# bms_master.net
KiCad netlist of a schematic drawn in EAGLE
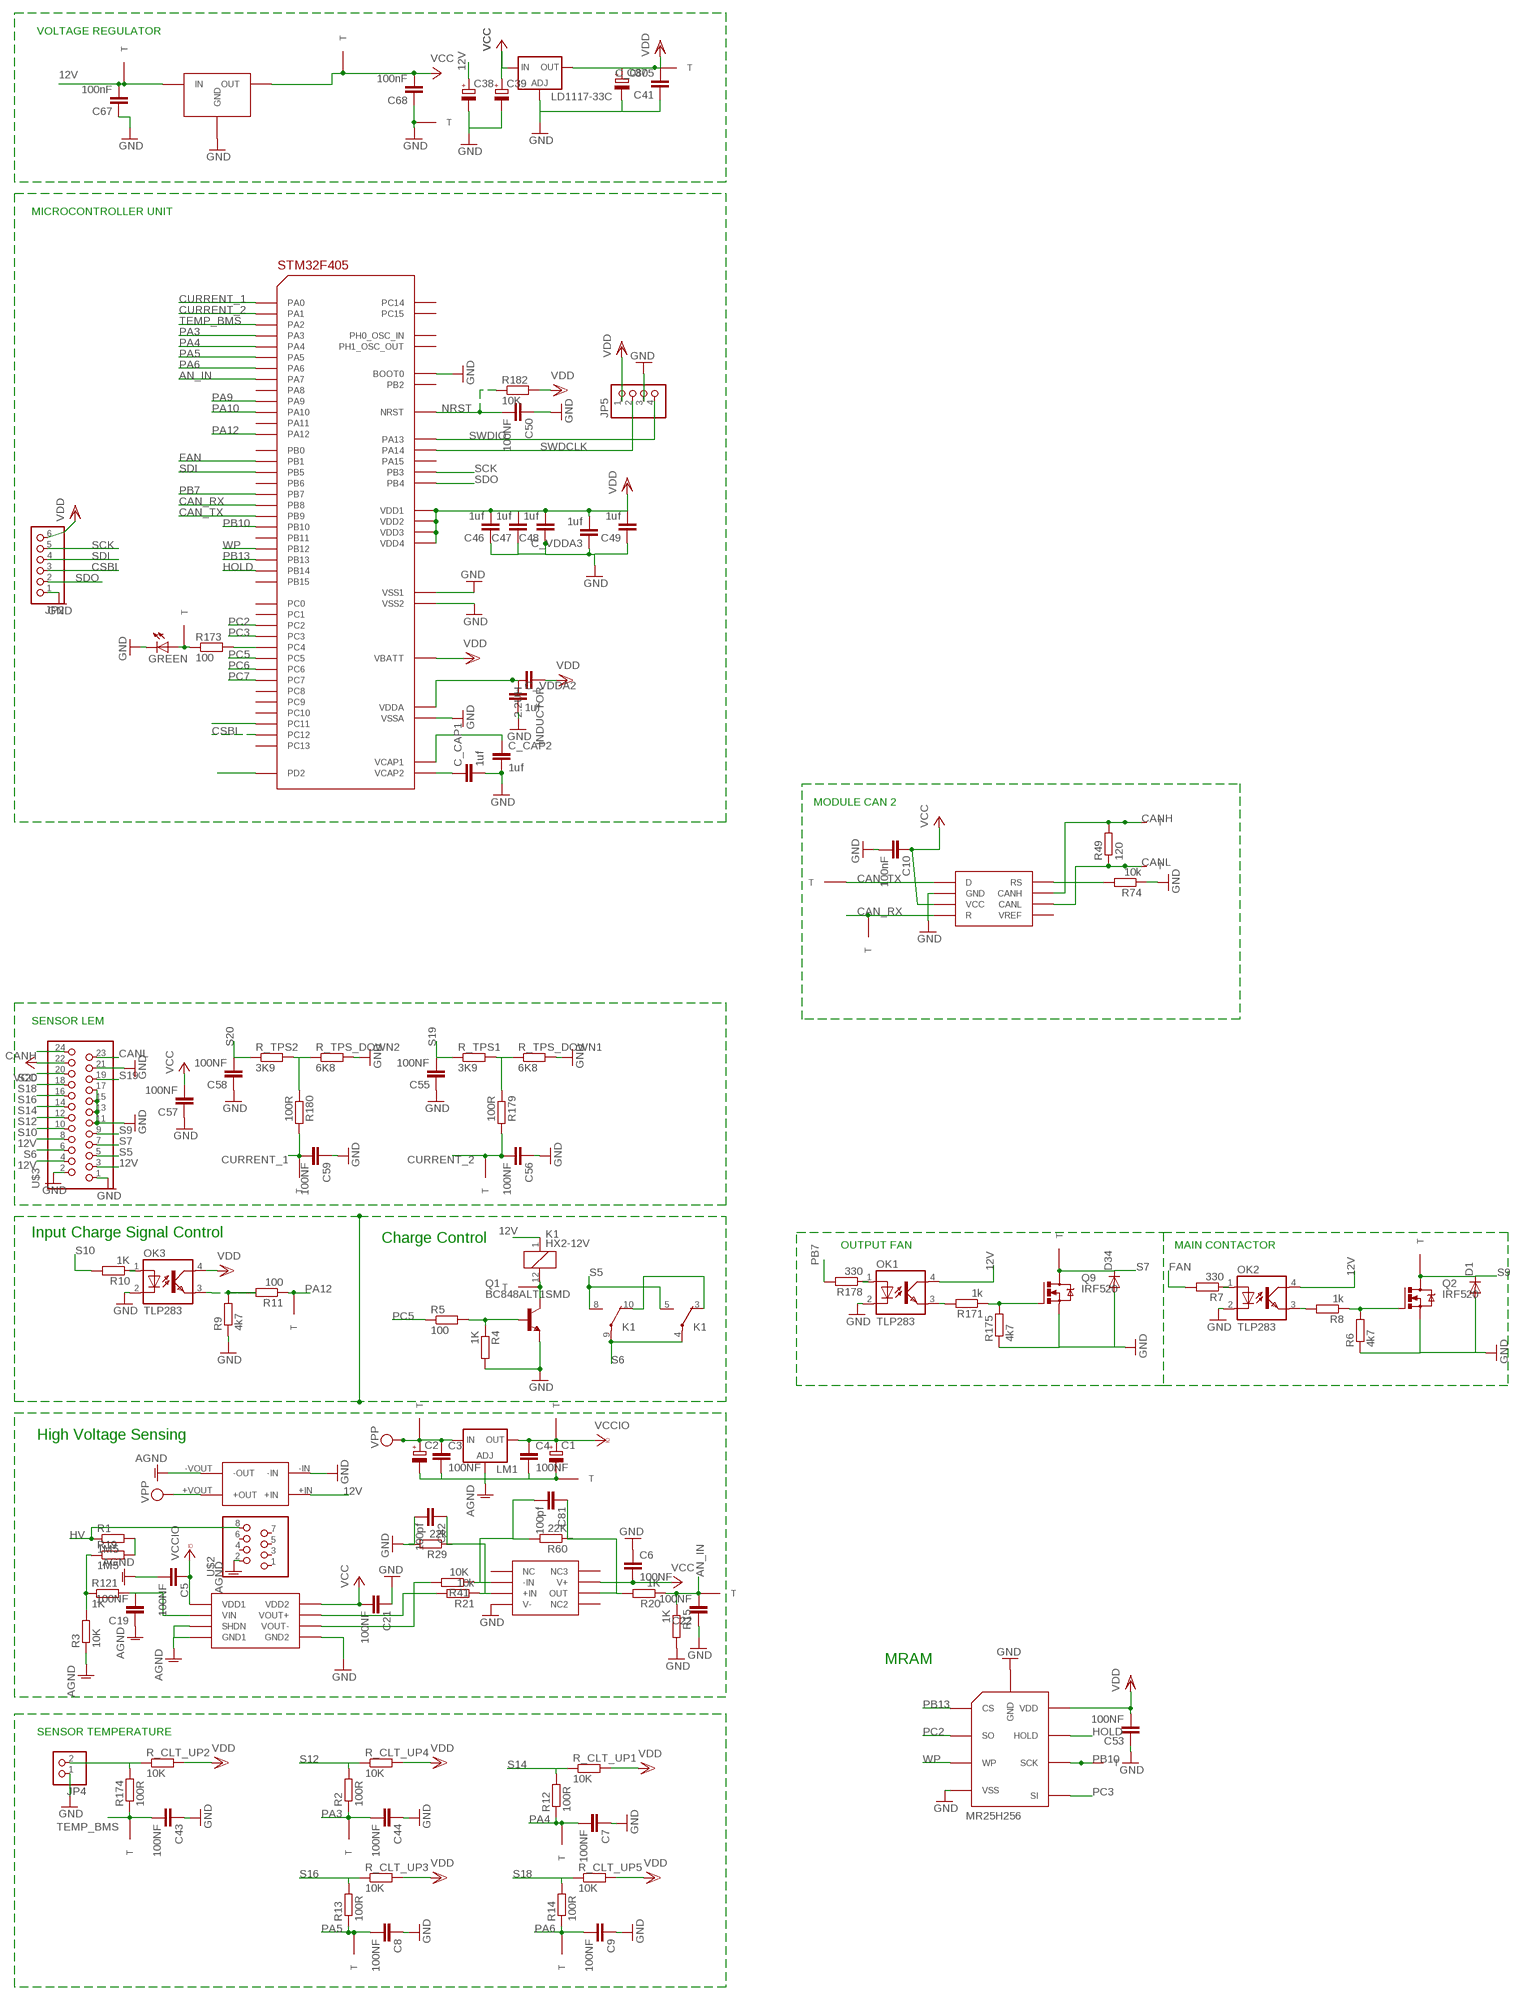
[diagram p0: schematic, sheet 1]

(export (version "E")
  (design (tool "Eeschema 10.0.6"))
  (components
    (comp (ref "C1")
      (value "CPOL-EU153CLV-0605")
      (footprint "eagle-import:153CLV-0605")
      (libsource (lib "eagle-import") (part "CPOL-EU153CLV-0605"))
    )
    (comp (ref "C2")
      (value "CPOL-EU153CLV-0810")
      (footprint "eagle-import:153CLV-0810")
      (libsource (lib "eagle-import") (part "CPOL-EU153CLV-0810"))
    )
    (comp (ref "C3")
      (value "100NF")
      (footprint "eagle-import:C_0805")
      (libsource (lib "eagle-import") (part "C_0805"))
    )
    (comp (ref "C4")
      (value "100NF")
      (footprint "eagle-import:C_0805")
      (libsource (lib "eagle-import") (part "C_0805"))
    )
    (comp (ref "C5")
      (value "100NF")
      (footprint "eagle-import:C_0805")
      (libsource (lib "eagle-import") (part "C_0805"))
    )
    (comp (ref "C6")
      (value "100NF")
      (footprint "eagle-import:C_0805")
      (libsource (lib "eagle-import") (part "C_0805"))
    )
    (comp (ref "C7")
      (value "100NF")
      (footprint "eagle-import:C_0805")
      (libsource (lib "eagle-import") (part "C_0805"))
    )
    (comp (ref "C8")
      (value "100NF")
      (footprint "eagle-import:C_0805")
      (libsource (lib "eagle-import") (part "C_0805"))
    )
    (comp (ref "C9")
      (value "100NF")
      (footprint "eagle-import:C_0805")
      (libsource (lib "eagle-import") (part "C_0805"))
    )
    (comp (ref "C10")
      (value "100nF")
      (footprint "eagle-import:C_0805")
      (libsource (lib "eagle-import") (part "C_0805"))
    )
    (comp (ref "C19")
      (value "100NF")
      (footprint "eagle-import:C_0805")
      (libsource (lib "eagle-import") (part "C_0805"))
    )
    (comp (ref "C21")
      (value "100NF")
      (footprint "eagle-import:C_0805")
      (libsource (lib "eagle-import") (part "C_0805"))
    )
    (comp (ref "C22")
      (value "100NF")
      (footprint "eagle-import:C_0805")
      (libsource (lib "eagle-import") (part "C_0805"))
    )
    (comp (ref "C37")
      (value "CPOL-EU153CLV-0605")
      (footprint "eagle-import:153CLV-0605")
      (libsource (lib "eagle-import") (part "CPOL-EU153CLV-0605"))
    )
    (comp (ref "C38")
      (value "CPOL-EU153CLV-0810")
      (footprint "eagle-import:153CLV-0810")
      (libsource (lib "eagle-import") (part "CPOL-EU153CLV-0810"))
    )
    (comp (ref "C39")
      (value "CPOL-EU153CLV-0605")
      (footprint "eagle-import:153CLV-0605")
      (libsource (lib "eagle-import") (part "CPOL-EU153CLV-0605"))
    )
    (comp (ref "C41")
      (value "C_0805")
      (footprint "eagle-import:C_0805")
      (libsource (lib "eagle-import") (part "C_0805"))
    )
    (comp (ref "C43")
      (value "100NF")
      (footprint "eagle-import:C_0805")
      (libsource (lib "eagle-import") (part "C_0805"))
    )
    (comp (ref "C44")
      (value "100NF")
      (footprint "eagle-import:C_0805")
      (libsource (lib "eagle-import") (part "C_0805"))
    )
    (comp (ref "C46")
      (value "1uf")
      (footprint "eagle-import:C_0805")
      (libsource (lib "eagle-import") (part "C_0805"))
    )
    (comp (ref "C47")
      (value "1uf")
      (footprint "eagle-import:C_0805")
      (libsource (lib "eagle-import") (part "C_0805"))
    )
    (comp (ref "C48")
      (value "1uf")
      (footprint "eagle-import:C_0805")
      (libsource (lib "eagle-import") (part "C_0805"))
    )
    (comp (ref "C49")
      (value "1uf")
      (footprint "eagle-import:C_0805")
      (libsource (lib "eagle-import") (part "C_0805"))
    )
    (comp (ref "C50")
      (value "100NF")
      (footprint "eagle-import:C_0805")
      (libsource (lib "eagle-import") (part "C_0805"))
    )
    (comp (ref "C53")
      (value "100NF")
      (footprint "eagle-import:C_0805")
      (libsource (lib "eagle-import") (part "C_0805"))
    )
    (comp (ref "C55")
      (value "100NF")
      (footprint "eagle-import:C_0805")
      (libsource (lib "eagle-import") (part "C_0805"))
    )
    (comp (ref "C56")
      (value "100NF")
      (footprint "eagle-import:C_0805")
      (libsource (lib "eagle-import") (part "C_0805"))
    )
    (comp (ref "C57")
      (value "100NF")
      (footprint "eagle-import:C_0805")
      (libsource (lib "eagle-import") (part "C_0805"))
    )
    (comp (ref "C58")
      (value "100NF")
      (footprint "eagle-import:C_0805")
      (libsource (lib "eagle-import") (part "C_0805"))
    )
    (comp (ref "C59")
      (value "100NF")
      (footprint "eagle-import:C_0805")
      (libsource (lib "eagle-import") (part "C_0805"))
    )
    (comp (ref "C67")
      (value "100nF")
      (footprint "eagle-import:C_0805")
      (libsource (lib "eagle-import") (part "C_0805"))
    )
    (comp (ref "C68")
      (value "100nF")
      (footprint "eagle-import:C_0805")
      (libsource (lib "eagle-import") (part "C_0805"))
    )
    (comp (ref "C81")
      (value "100pf")
      (footprint "eagle-import:C_0805")
      (libsource (lib "eagle-import") (part "C_0805"))
    )
    (comp (ref "C82")
      (value "100pf")
      (footprint "eagle-import:C_0805")
      (libsource (lib "eagle-import") (part "C_0805"))
    )
    (comp (ref "C_CAP1")
      (value "1uf")
      (footprint "eagle-import:C_0805")
      (libsource (lib "eagle-import") (part "C_0805"))
    )
    (comp (ref "C_CAP2")
      (value "1uf")
      (footprint "eagle-import:C_0805")
      (libsource (lib "eagle-import") (part "C_0805"))
    )
    (comp (ref "C_VDDA2")
      (value "1uf")
      (footprint "eagle-import:C_0805")
      (libsource (lib "eagle-import") (part "C_0805"))
    )
    (comp (ref "C_VDDA3")
      (value "1uf")
      (footprint "eagle-import:C_0805")
      (libsource (lib "eagle-import") (part "C_0805"))
    )
    (comp (ref "D1")
      (value "DIODE-SOD80C")
      (footprint "eagle-import:SOD80C")
      (libsource (lib "eagle-import") (part "DIODE-SOD80C"))
    )
    (comp (ref "D34")
      (value "DIODE-SOD80C")
      (footprint "eagle-import:SOD80C")
      (libsource (lib "eagle-import") (part "DIODE-SOD80C"))
    )
    (comp (ref "GREEN")
      (value "LED3MM")
      (footprint "eagle-import:LED3MM")
      (libsource (lib "eagle-import") (part "LED3MM"))
    )
    (comp (ref "INDUCTOR")
      (value "2.2UH")
      (footprint "eagle-import:C0805K")
      (libsource (lib "eagle-import") (part "C-EUC0805K"))
    )
    (comp (ref "JP2")
      (value "PINHD-1X6")
      (footprint "eagle-import:1X06")
      (libsource (lib "eagle-import") (part "PINHD-1X6"))
    )
    (comp (ref "JP4")
      (value "PINHD-1X2/90")
      (footprint "eagle-import:1X02_90")
      (libsource (lib "eagle-import") (part "PINHD-1X2/90"))
    )
    (comp (ref "JP5")
      (value "PINHD-1X4")
      (footprint "eagle-import:1X04")
      (libsource (lib "eagle-import") (part "PINHD-1X4"))
    )
    (comp (ref "K1")
      (value "HX2-12V")
      (footprint "eagle-import:HX")
      (libsource (lib "eagle-import") (part "HX2-12V"))
    )
    (comp (ref "LD1117-33C")
      (value "LM317MABDT")
      (footprint "eagle-import:DPACK@1")
      (libsource (lib "eagle-import") (part "v-reg_LM317?MABDT"))
    )
    (comp (ref "LM1")
      (value "LM317MABDT")
      (footprint "eagle-import:DPACK@1")
      (libsource (lib "eagle-import") (part "v-reg_LM317?MABDT"))
    )
    (comp (ref "OK1")
      (value "TLP283")
      (footprint "eagle-import:MINI-FLAT-4")
      (libsource (lib "eagle-import") (part "TLP283"))
    )
    (comp (ref "OK2")
      (value "TLP283")
      (footprint "eagle-import:MINI-FLAT-4")
      (libsource (lib "eagle-import") (part "TLP283"))
    )
    (comp (ref "OK3")
      (value "TLP283")
      (footprint "eagle-import:MINI-FLAT-4")
      (libsource (lib "eagle-import") (part "TLP283"))
    )
    (comp (ref "Q1")
      (value "BC848ALT1SMD")
      (footprint "eagle-import:SOT23")
      (libsource (lib "eagle-import") (part "BC848SMDALT1"))
    )
    (comp (ref "Q2")
      (value "IRF520")
      (footprint "eagle-import:D-PAK_TO252AA")
      (libsource (lib "eagle-import") (part "IRF520"))
    )
    (comp (ref "Q9")
      (value "IRF520")
      (footprint "eagle-import:D-PAK_TO252AA")
      (libsource (lib "eagle-import") (part "IRF520"))
    )
    (comp (ref "R1")
      (value "1M5")
      (footprint "eagle-import:R1210")
      (libsource (lib "eagle-import") (part "R_1210"))
    )
    (comp (ref "R2")
      (value "100R")
      (footprint "eagle-import:R_0805")
      (libsource (lib "eagle-import") (part "R_EU"))
    )
    (comp (ref "R3")
      (value "10K")
      (footprint "eagle-import:R1210")
      (libsource (lib "eagle-import") (part "R_1210"))
    )
    (comp (ref "R4")
      (value "1K")
      (footprint "eagle-import:R_0805")
      (libsource (lib "eagle-import") (part "R_EU"))
    )
    (comp (ref "R5")
      (value "100")
      (footprint "eagle-import:R_0805")
      (libsource (lib "eagle-import") (part "R_EU"))
    )
    (comp (ref "R6")
      (value "4k7")
      (footprint "eagle-import:R_0805")
      (libsource (lib "eagle-import") (part "R_EU"))
    )
    (comp (ref "R7")
      (value "330")
      (footprint "eagle-import:R_0805")
      (libsource (lib "eagle-import") (part "R_EU"))
    )
    (comp (ref "R8")
      (value "1k")
      (footprint "eagle-import:R_0805")
      (libsource (lib "eagle-import") (part "R_EU"))
    )
    (comp (ref "R9")
      (value "4k7")
      (footprint "eagle-import:R_0805")
      (libsource (lib "eagle-import") (part "R_EU"))
    )
    (comp (ref "R10")
      (value "1K")
      (footprint "eagle-import:R_0805")
      (libsource (lib "eagle-import") (part "R_EU"))
    )
    (comp (ref "R11")
      (value "100")
      (footprint "eagle-import:R_0805")
      (libsource (lib "eagle-import") (part "R_EU"))
    )
    (comp (ref "R12")
      (value "100R")
      (footprint "eagle-import:R_0805")
      (libsource (lib "eagle-import") (part "R_EU"))
    )
    (comp (ref "R13")
      (value "100R")
      (footprint "eagle-import:R_0805")
      (libsource (lib "eagle-import") (part "R_EU"))
    )
    (comp (ref "R14")
      (value "100R")
      (footprint "eagle-import:R_0805")
      (libsource (lib "eagle-import") (part "R_EU"))
    )
    (comp (ref "R15")
      (value "1K")
      (footprint "eagle-import:R_0805")
      (libsource (lib "eagle-import") (part "R_EU"))
    )
    (comp (ref "R19")
      (value "1M5")
      (footprint "eagle-import:R1210")
      (libsource (lib "eagle-import") (part "R_1210"))
    )
    (comp (ref "R20")
      (value "1K")
      (footprint "eagle-import:R_0805")
      (libsource (lib "eagle-import") (part "R_EU"))
    )
    (comp (ref "R21")
      (value "10k")
      (footprint "eagle-import:R_0805")
      (libsource (lib "eagle-import") (part "R_EU"))
    )
    (comp (ref "R29")
      (value "22k")
      (footprint "eagle-import:R_0805")
      (libsource (lib "eagle-import") (part "R_EU"))
    )
    (comp (ref "R41")
      (value "10K")
      (footprint "eagle-import:R_0805")
      (libsource (lib "eagle-import") (part "R_EU"))
    )
    (comp (ref "R49")
      (value "120")
      (footprint "eagle-import:0207_7")
      (libsource (lib "eagle-import") (part "R-EU_0207/7"))
    )
    (comp (ref "R60")
      (value "22K")
      (footprint "eagle-import:R_0805")
      (libsource (lib "eagle-import") (part "R_EU"))
    )
    (comp (ref "R74")
      (value "10k")
      (footprint "eagle-import:R_0805")
      (libsource (lib "eagle-import") (part "R_EU"))
    )
    (comp (ref "R121")
      (value "1K")
      (footprint "eagle-import:R_1210")
      (libsource (lib "eagle-import") (part "IVC_R_1210"))
    )
    (comp (ref "R171")
      (value "1k")
      (footprint "eagle-import:R_0805")
      (libsource (lib "eagle-import") (part "R_EU"))
    )
    (comp (ref "R173")
      (value "100")
      (footprint "eagle-import:R_0805")
      (libsource (lib "eagle-import") (part "R_EU"))
    )
    (comp (ref "R174")
      (value "100R")
      (footprint "eagle-import:R_0805")
      (libsource (lib "eagle-import") (part "R_EU"))
    )
    (comp (ref "R175")
      (value "4k7")
      (footprint "eagle-import:R_0805")
      (libsource (lib "eagle-import") (part "R_EU"))
    )
    (comp (ref "R178")
      (value "330")
      (footprint "eagle-import:R_0805")
      (libsource (lib "eagle-import") (part "R_EU"))
    )
    (comp (ref "R179")
      (value "100R")
      (footprint "eagle-import:R_0805")
      (libsource (lib "eagle-import") (part "R_EU"))
    )
    (comp (ref "R180")
      (value "100R")
      (footprint "eagle-import:R_0805")
      (libsource (lib "eagle-import") (part "R_EU"))
    )
    (comp (ref "R182")
      (value "10K")
      (footprint "eagle-import:R_0805")
      (libsource (lib "eagle-import") (part "R_EU"))
    )
    (comp (ref "R_CLT_UP1")
      (value "10K")
      (footprint "eagle-import:R_0805")
      (libsource (lib "eagle-import") (part "R_EU"))
    )
    (comp (ref "R_CLT_UP2")
      (value "10K")
      (footprint "eagle-import:R_0805")
      (libsource (lib "eagle-import") (part "R_EU"))
    )
    (comp (ref "R_CLT_UP3")
      (value "10K")
      (footprint "eagle-import:R_0805")
      (libsource (lib "eagle-import") (part "R_EU"))
    )
    (comp (ref "R_CLT_UP4")
      (value "10K")
      (footprint "eagle-import:R_0805")
      (libsource (lib "eagle-import") (part "R_EU"))
    )
    (comp (ref "R_CLT_UP5")
      (value "10K")
      (footprint "eagle-import:R_0805")
      (libsource (lib "eagle-import") (part "R_EU"))
    )
    (comp (ref "R_TPS1")
      (value "3K9")
      (footprint "eagle-import:R_0805")
      (libsource (lib "eagle-import") (part "R_EU"))
    )
    (comp (ref "R_TPS2")
      (value "3K9")
      (footprint "eagle-import:R_0805")
      (libsource (lib "eagle-import") (part "R_EU"))
    )
    (comp (ref "R_TPS_DOWN1")
      (value "6K8")
      (footprint "eagle-import:R_0805")
      (libsource (lib "eagle-import") (part "R_EU"))
    )
    (comp (ref "R_TPS_DOWN2")
      (value "6K8")
      (footprint "eagle-import:R_0805")
      (libsource (lib "eagle-import") (part "R_EU"))
    )
    (comp (ref "U$1")
      (value "NWD5-12")
      (footprint "eagle-import:NWD5")
      (libsource (lib "eagle-import") (part "NWD5-12"))
    )
    (comp (ref "U$2")
      (value "SOCKET8P")
      (footprint "eagle-import:8PIN")
      (libsource (lib "eagle-import") (part "SOCKET8P"))
    )
    (comp (ref "U$3")
      (value "SOCKET24P")
      (footprint "eagle-import:24PIN")
      (libsource (lib "eagle-import") (part "SOCKET24P"))
    )
    (comp (ref "U$4")
      (value "TESTPOINT")
      (footprint "eagle-import:TESTPOINT")
      (libsource (lib "eagle-import") (part "TESTPOINT"))
    )
    (comp (ref "U$5")
      (value "TESTPOINT")
      (footprint "eagle-import:TESTPOINT")
      (libsource (lib "eagle-import") (part "TESTPOINT"))
    )
    (comp (ref "U$6")
      (value "TESTPOINT")
      (footprint "eagle-import:TESTPOINT")
      (libsource (lib "eagle-import") (part "TESTPOINT"))
    )
    (comp (ref "U$7")
      (value "TESTPOINT")
      (footprint "eagle-import:TESTPOINT")
      (libsource (lib "eagle-import") (part "TESTPOINT"))
    )
    (comp (ref "U$8")
      (value "TESTPOINT")
      (footprint "eagle-import:TESTPOINT")
      (libsource (lib "eagle-import") (part "TESTPOINT"))
    )
    (comp (ref "U$9")
      (value "ACPL-C87B")
      (footprint "eagle-import:STRETCHSO8")
      (libsource (lib "eagle-import") (part "ACPL-C87B"))
    )
    (comp (ref "U$10")
      (value "TESTPOINT")
      (footprint "eagle-import:TESTPOINT")
      (libsource (lib "eagle-import") (part "TESTPOINT"))
    )
    (comp (ref "U$11")
      (value "TESTPOINT")
      (footprint "eagle-import:TESTPOINT")
      (libsource (lib "eagle-import") (part "TESTPOINT"))
    )
    (comp (ref "U$12")
      (value "TESTPOINT")
      (footprint "eagle-import:TESTPOINT")
      (libsource (lib "eagle-import") (part "TESTPOINT"))
    )
    (comp (ref "U$13")
      (value "TESTPOINT")
      (footprint "eagle-import:TESTPOINT")
      (libsource (lib "eagle-import") (part "TESTPOINT"))
    )
    (comp (ref "U$14")
      (value "TESTPOINT")
      (footprint "eagle-import:TESTPOINT")
      (libsource (lib "eagle-import") (part "TESTPOINT"))
    )
    (comp (ref "U$15")
      (value "TESTPOINT")
      (footprint "eagle-import:TESTPOINT")
      (libsource (lib "eagle-import") (part "TESTPOINT"))
    )
    (comp (ref "U$16")
      (value "TESTPOINT")
      (footprint "eagle-import:TESTPOINT")
      (libsource (lib "eagle-import") (part "TESTPOINT"))
    )
    (comp (ref "U$17")
      (value "TESTPOINT")
      (footprint "eagle-import:TESTPOINT")
      (libsource (lib "eagle-import") (part "TESTPOINT"))
    )
    (comp (ref "U$18")
      (value "TESTPOINT")
      (footprint "eagle-import:TESTPOINT")
      (libsource (lib "eagle-import") (part "TESTPOINT"))
    )
    (comp (ref "U$19")
      (value "TESTPOINT")
      (footprint "eagle-import:TESTPOINT")
      (libsource (lib "eagle-import") (part "TESTPOINT"))
    )
    (comp (ref "U$20")
      (value "TESTPOINT")
      (footprint "eagle-import:TESTPOINT")
      (libsource (lib "eagle-import") (part "TESTPOINT"))
    )
    (comp (ref "U$21")
      (value "TESTPOINT")
      (footprint "eagle-import:TESTPOINT")
      (libsource (lib "eagle-import") (part "TESTPOINT"))
    )
    (comp (ref "U$22")
      (value "TESTPOINT")
      (footprint "eagle-import:TESTPOINT")
      (libsource (lib "eagle-import") (part "TESTPOINT"))
    )
    (comp (ref "U$23")
      (value "TESTPOINT")
      (footprint "eagle-import:TESTPOINT")
      (libsource (lib "eagle-import") (part "TESTPOINT"))
    )
    (comp (ref "U$24")
      (value "TESTPOINT")
      (footprint "eagle-import:TESTPOINT")
      (libsource (lib "eagle-import") (part "TESTPOINT"))
    )
    (comp (ref "U$25")
      (value "TESTPOINT")
      (footprint "eagle-import:TESTPOINT")
      (libsource (lib "eagle-import") (part "TESTPOINT"))
    )
    (comp (ref "U$26")
      (value "TESTPOINT")
      (footprint "eagle-import:TESTPOINT")
      (libsource (lib "eagle-import") (part "TESTPOINT"))
    )
    (comp (ref "U$27")
      (value "TESTPOINT")
      (footprint "eagle-import:TESTPOINT")
      (libsource (lib "eagle-import") (part "TESTPOINT"))
    )
    (comp (ref "U$28")
      (value "TESTPOINT")
      (footprint "eagle-import:TESTPOINT")
      (libsource (lib "eagle-import") (part "TESTPOINT"))
    )
    (comp (ref "U$29")
      (value "OKI-78SR-5")
      (footprint "eagle-import:MDC_OKI")
      (libsource (lib "eagle-import") (part "OKI-78SR-5"))
    )
    (comp (ref "U$31")
      (value "STM32F405")
      (footprint "eagle-import:TQFP64")
      (libsource (lib "eagle-import") (part "STM32F405"))
    )
    (comp (ref "U$32")
      (value "MR25H256")
      (footprint "eagle-import:8DFN")
      (libsource (lib "eagle-import") (part "MR25H256"))
    )
    (comp (ref "U$35")
      (value "TESTPOINT")
      (footprint "eagle-import:TESTPOINT")
      (libsource (lib "eagle-import") (part "TESTPOINT"))
    )
    (comp (ref "U$70")
      (value "OPA237")
      (footprint "eagle-import:SO-08")
      (libsource (lib "eagle-import") (part "OPA237"))
    )
    (comp (ref "U8")
      (value "MCP2551")
      (footprint "eagle-import:SN65HVD230")
      (libsource (lib "eagle-import") (part "SN65HVD230"))
    )
  )
  (nets
    (net (code "1") (name "/12V") (class "Default")
      (node (ref "C38") (pin "+") (pinfunction "+_+") (pintype "passive"))
      (node (ref "C67") (pin "2") (pinfunction "2_2") (pintype "passive"))
      (node (ref "K1") (pin "1") (pinfunction "1_1") (pintype "passive"))
      (node (ref "OK1") (pin "4") (pinfunction "COL_4") (pintype "passive"))
      (node (ref "OK2") (pin "4") (pinfunction "COL_4") (pintype "passive"))
      (node (ref "U$1") (pin "+IN") (pinfunction "+IN_+IN") (pintype "bidirectional"))
      (node (ref "U$29") (pin "1") (pinfunction "IN_1") (pintype "bidirectional"))
      (node (ref "U$3") (pin "3") (pinfunction "3_3") (pintype "passive"))
      (node (ref "U$3") (pin "4") (pinfunction "4_4") (pintype "passive"))
      (node (ref "U$3") (pin "8") (pinfunction "8_8") (pintype "passive"))
      (node (ref "U$5") (pin "P$1") (pinfunction "T_P$1") (pintype "bidirectional"))
    )
    (net (code "2") (name "/AN_IN") (class "Default")
      (node (ref "C22") (pin "2") (pinfunction "2_2") (pintype "passive"))
      (node (ref "R15") (pin "1") (pinfunction "1_1") (pintype "passive"))
      (node (ref "R20") (pin "1") (pinfunction "1_1") (pintype "passive"))
      (node (ref "U$22") (pin "P$1") (pinfunction "T_P$1") (pintype "bidirectional"))
      (node (ref "U$31") (pin "23") (pinfunction "PA7_23") (pintype "bidirectional"))
    )
    (net (code "3") (name "/CANH") (class "Default")
      (node (ref "R49") (pin "2") (pinfunction "2_2") (pintype "passive"))
      (node (ref "U$12") (pin "P$1") (pinfunction "T_P$1") (pintype "bidirectional"))
      (node (ref "U$3") (pin "24") (pinfunction "24_24") (pintype "passive"))
      (node (ref "U8") (pin "P$7") (pinfunction "CANH_P$7") (pintype "bidirectional"))
    )
    (net (code "4") (name "/CANL") (class "Default")
      (node (ref "R49") (pin "1") (pinfunction "1_1") (pintype "passive"))
      (node (ref "U$11") (pin "P$1") (pinfunction "T_P$1") (pintype "bidirectional"))
      (node (ref "U$3") (pin "23") (pinfunction "23_23") (pintype "passive"))
      (node (ref "U8") (pin "P$6") (pinfunction "CANL_P$6") (pintype "bidirectional"))
    )
    (net (code "5") (name "/CAN_RX") (class "Default")
      (node (ref "U$31") (pin "61") (pinfunction "PB8_61") (pintype "bidirectional"))
      (node (ref "U$8") (pin "P$1") (pinfunction "T_P$1") (pintype "bidirectional"))
      (node (ref "U8") (pin "P$4") (pinfunction "R_P$4") (pintype "bidirectional"))
    )
    (net (code "6") (name "/CAN_TX") (class "Default")
      (node (ref "U$10") (pin "P$1") (pinfunction "T_P$1") (pintype "bidirectional"))
      (node (ref "U$31") (pin "62") (pinfunction "PB9_62") (pintype "bidirectional"))
      (node (ref "U8") (pin "P$1") (pinfunction "D_P$1") (pintype "bidirectional"))
    )
    (net (code "7") (name "/CSBI") (class "Default")
      (node (ref "JP2") (pin "3") (pinfunction "3_3") (pintype "passive"))
      (node (ref "U$31") (pin "53") (pinfunction "PC12_53") (pintype "bidirectional"))
    )
    (net (code "8") (name "/CURRENT_1") (class "Default")
      (node (ref "C59") (pin "2") (pinfunction "2_2") (pintype "passive"))
      (node (ref "R180") (pin "2") (pinfunction "2_2") (pintype "passive"))
      (node (ref "U$14") (pin "P$1") (pinfunction "T_P$1") (pintype "bidirectional"))
      (node (ref "U$31") (pin "14") (pinfunction "PA0_14") (pintype "bidirectional"))
    )
    (net (code "9") (name "/CURRENT_2") (class "Default")
      (node (ref "C56") (pin "2") (pinfunction "2_2") (pintype "passive"))
      (node (ref "R179") (pin "2") (pinfunction "2_2") (pintype "passive"))
      (node (ref "U$13") (pin "P$1") (pinfunction "T_P$1") (pintype "bidirectional"))
      (node (ref "U$31") (pin "15") (pinfunction "PA1_15") (pintype "bidirectional"))
    )
    (net (code "10") (name "/FAN") (class "Default")
      (node (ref "R7") (pin "2") (pinfunction "2_2") (pintype "passive"))
      (node (ref "U$31") (pin "27") (pinfunction "PB1_27") (pintype "bidirectional"))
    )
    (net (code "11") (name "/HOLD") (class "Default")
      (node (ref "U$31") (pin "35") (pinfunction "PB14_35") (pintype "bidirectional"))
      (node (ref "U$32") (pin "P$7") (pinfunction "HOLD_P$7") (pintype "bidirectional"))
    )
    (net (code "12") (name "/HV") (class "Default")
      (node (ref "R1") (pin "1") (pinfunction "1_1") (pintype "passive"))
      (node (ref "U$2") (pin "8") (pinfunction "8_8") (pintype "passive"))
    )
    (net (code "13") (name "/NRST") (class "Default")
      (node (ref "C50") (pin "2") (pinfunction "2_2") (pintype "passive"))
      (node (ref "R182") (pin "1") (pinfunction "1_1") (pintype "passive"))
      (node (ref "U$31") (pin "7") (pinfunction "NRST_7") (pintype "bidirectional"))
    )
    (net (code "14") (name "/PA3") (class "Default")
      (node (ref "C44") (pin "2") (pinfunction "2_2") (pintype "passive"))
      (node (ref "R2") (pin "1") (pinfunction "1_1") (pintype "passive"))
      (node (ref "U$24") (pin "P$1") (pinfunction "T_P$1") (pintype "bidirectional"))
      (node (ref "U$31") (pin "17") (pinfunction "PA3_17") (pintype "bidirectional"))
    )
    (net (code "15") (name "/PA4") (class "Default")
      (node (ref "C7") (pin "2") (pinfunction "2_2") (pintype "passive"))
      (node (ref "R12") (pin "1") (pinfunction "1_1") (pintype "passive"))
      (node (ref "U$27") (pin "P$1") (pinfunction "T_P$1") (pintype "bidirectional"))
      (node (ref "U$31") (pin "20") (pinfunction "PA4_20") (pintype "bidirectional"))
    )
    (net (code "16") (name "/PA5") (class "Default")
      (node (ref "C8") (pin "2") (pinfunction "2_2") (pintype "passive"))
      (node (ref "R13") (pin "1") (pinfunction "1_1") (pintype "passive"))
      (node (ref "U$25") (pin "P$1") (pinfunction "T_P$1") (pintype "bidirectional"))
      (node (ref "U$31") (pin "21") (pinfunction "PA5_21") (pintype "bidirectional"))
    )
    (net (code "17") (name "/PA6") (class "Default")
      (node (ref "C9") (pin "2") (pinfunction "2_2") (pintype "passive"))
      (node (ref "R14") (pin "1") (pinfunction "1_1") (pintype "passive"))
      (node (ref "U$26") (pin "P$1") (pinfunction "T_P$1") (pintype "bidirectional"))
      (node (ref "U$31") (pin "22") (pinfunction "PA6_22") (pintype "bidirectional"))
    )
    (net (code "18") (name "/PA9") (class "Default")
      (node (ref "U$31") (pin "42") (pinfunction "PA9_42") (pintype "bidirectional"))
    )
    (net (code "19") (name "/PA10") (class "Default")
      (node (ref "U$31") (pin "43") (pinfunction "PA10_43") (pintype "bidirectional"))
    )
    (net (code "20") (name "/PA12") (class "Default")
      (node (ref "R11") (pin "1") (pinfunction "1_1") (pintype "passive"))
      (node (ref "U$15") (pin "P$1") (pinfunction "T_P$1") (pintype "bidirectional"))
      (node (ref "U$31") (pin "45") (pinfunction "PA12_45") (pintype "bidirectional"))
    )
    (net (code "21") (name "/PB7") (class "Default")
      (node (ref "R178") (pin "2") (pinfunction "2_2") (pintype "passive"))
      (node (ref "U$31") (pin "59") (pinfunction "PB7_59") (pintype "bidirectional"))
    )
    (net (code "22") (name "/PB10") (class "Default")
      (node (ref "U$28") (pin "P$1") (pinfunction "T_P$1") (pintype "bidirectional"))
      (node (ref "U$31") (pin "29") (pinfunction "PB10_29") (pintype "bidirectional"))
      (node (ref "U$32") (pin "P$6") (pinfunction "SCK_P$6") (pintype "bidirectional"))
    )
    (net (code "23") (name "/PB13") (class "Default")
      (node (ref "U$31") (pin "34") (pinfunction "PB13_34") (pintype "bidirectional"))
      (node (ref "U$32") (pin "P$1") (pinfunction "CS_P$1") (pintype "bidirectional"))
    )
    (net (code "24") (name "/PC2") (class "Default")
      (node (ref "U$31") (pin "10") (pinfunction "PC2_10") (pintype "bidirectional"))
      (node (ref "U$32") (pin "P$2") (pinfunction "SO_P$2") (pintype "bidirectional"))
    )
    (net (code "25") (name "/PC3") (class "Default")
      (node (ref "U$31") (pin "11") (pinfunction "PC3_11") (pintype "bidirectional"))
      (node (ref "U$32") (pin "P$5") (pinfunction "SI_P$5") (pintype "bidirectional"))
    )
    (net (code "26") (name "/PC5") (class "Default")
      (node (ref "R5") (pin "1") (pinfunction "1_1") (pintype "passive"))
      (node (ref "U$31") (pin "25") (pinfunction "PC5_25") (pintype "bidirectional"))
    )
    (net (code "27") (name "/PC6") (class "Default")
      (node (ref "U$31") (pin "37") (pinfunction "PC6_37") (pintype "bidirectional"))
    )
    (net (code "28") (name "/PC7") (class "Default")
      (node (ref "U$31") (pin "38") (pinfunction "PC7_38") (pintype "bidirectional"))
    )
    (net (code "29") (name "/S5") (class "Default")
      (node (ref "K1") (pin "5") (pinfunction "S_5") (pintype "passive"))
      (node (ref "K1") (pin "8") (pinfunction "S_8") (pintype "passive"))
      (node (ref "U$3") (pin "5") (pinfunction "5_5") (pintype "passive"))
    )
    (net (code "30") (name "/S6") (class "Default")
      (node (ref "K1") (pin "4") (pinfunction "P_4") (pintype "passive"))
      (node (ref "K1") (pin "9") (pinfunction "P_9") (pintype "passive"))
      (node (ref "U$3") (pin "6") (pinfunction "6_6") (pintype "passive"))
    )
    (net (code "31") (name "/S7") (class "Default")
      (node (ref "D34") (pin "C") (pinfunction "C_C") (pintype "passive"))
      (node (ref "Q9") (pin "4") (pinfunction "D_4") (pintype "passive"))
      (node (ref "U$17") (pin "P$1") (pinfunction "T_P$1") (pintype "bidirectional"))
      (node (ref "U$3") (pin "7") (pinfunction "7_7") (pintype "passive"))
    )
    (net (code "32") (name "/S9") (class "Default")
      (node (ref "D1") (pin "C") (pinfunction "C_C") (pintype "passive"))
      (node (ref "Q2") (pin "4") (pinfunction "D_4") (pintype "passive"))
      (node (ref "U$18") (pin "P$1") (pinfunction "T_P$1") (pintype "bidirectional"))
      (node (ref "U$3") (pin "9") (pinfunction "9_9") (pintype "passive"))
    )
    (net (code "33") (name "/S10") (class "Default")
      (node (ref "R10") (pin "2") (pinfunction "2_2") (pintype "passive"))
      (node (ref "U$3") (pin "10") (pinfunction "10_10") (pintype "passive"))
    )
    (net (code "34") (name "/S12") (class "Default")
      (node (ref "R2") (pin "2") (pinfunction "2_2") (pintype "passive"))
      (node (ref "R_CLT_UP4") (pin "1") (pinfunction "1_1") (pintype "passive"))
      (node (ref "U$3") (pin "12") (pinfunction "12_12") (pintype "passive"))
    )
    (net (code "35") (name "/S14") (class "Default")
      (node (ref "R12") (pin "2") (pinfunction "2_2") (pintype "passive"))
      (node (ref "R_CLT_UP1") (pin "1") (pinfunction "1_1") (pintype "passive"))
      (node (ref "U$3") (pin "14") (pinfunction "14_14") (pintype "passive"))
    )
    (net (code "36") (name "/S16") (class "Default")
      (node (ref "R13") (pin "2") (pinfunction "2_2") (pintype "passive"))
      (node (ref "R_CLT_UP3") (pin "1") (pinfunction "1_1") (pintype "passive"))
      (node (ref "U$3") (pin "16") (pinfunction "16_16") (pintype "passive"))
    )
    (net (code "37") (name "/S18") (class "Default")
      (node (ref "R14") (pin "2") (pinfunction "2_2") (pintype "passive"))
      (node (ref "R_CLT_UP5") (pin "1") (pinfunction "1_1") (pintype "passive"))
      (node (ref "U$3") (pin "18") (pinfunction "18_18") (pintype "passive"))
    )
    (net (code "38") (name "/S19") (class "Default")
      (node (ref "C55") (pin "2") (pinfunction "2_2") (pintype "passive"))
      (node (ref "R_TPS1") (pin "1") (pinfunction "1_1") (pintype "passive"))
      (node (ref "U$3") (pin "19") (pinfunction "19_19") (pintype "passive"))
    )
    (net (code "39") (name "/S20") (class "Default")
      (node (ref "C58") (pin "2") (pinfunction "2_2") (pintype "passive"))
      (node (ref "R_TPS2") (pin "1") (pinfunction "1_1") (pintype "passive"))
      (node (ref "U$3") (pin "20") (pinfunction "20_20") (pintype "passive"))
    )
    (net (code "40") (name "/SCK") (class "Default")
      (node (ref "JP2") (pin "5") (pinfunction "5_5") (pintype "passive"))
      (node (ref "U$31") (pin "55") (pinfunction "PB3_55") (pintype "bidirectional"))
    )
    (net (code "41") (name "/SDI") (class "Default")
      (node (ref "JP2") (pin "4") (pinfunction "4_4") (pintype "passive"))
      (node (ref "U$31") (pin "57") (pinfunction "PB5_57") (pintype "bidirectional"))
    )
    (net (code "42") (name "/SDO") (class "Default")
      (node (ref "JP2") (pin "2") (pinfunction "2_2") (pintype "passive"))
      (node (ref "U$31") (pin "56") (pinfunction "PB4_56") (pintype "bidirectional"))
    )
    (net (code "43") (name "/SWDCLK") (class "Default")
      (node (ref "JP5") (pin "2") (pinfunction "2_2") (pintype "passive"))
      (node (ref "U$31") (pin "49") (pinfunction "PA14_49") (pintype "bidirectional"))
    )
    (net (code "44") (name "/SWDIO") (class "Default")
      (node (ref "JP5") (pin "4") (pinfunction "4_4") (pintype "passive"))
      (node (ref "U$31") (pin "46") (pinfunction "PA13_46") (pintype "bidirectional"))
    )
    (net (code "45") (name "/TEMP_BMS") (class "Default")
      (node (ref "C43") (pin "2") (pinfunction "2_2") (pintype "passive"))
      (node (ref "R174") (pin "1") (pinfunction "1_1") (pintype "passive"))
      (node (ref "U$23") (pin "P$1") (pinfunction "T_P$1") (pintype "bidirectional"))
      (node (ref "U$31") (pin "16") (pinfunction "PA2_16") (pintype "bidirectional"))
    )
    (net (code "46") (name "/WP") (class "Default")
      (node (ref "U$31") (pin "33") (pinfunction "PB12_33") (pintype "bidirectional"))
      (node (ref "U$32") (pin "P$3") (pinfunction "WP_P$3") (pintype "bidirectional"))
    )
    (net (code "47") (name "AGND") (class "Default")
      (node (ref "C1") (pin "-") (pinfunction "-_-") (pintype "passive"))
      (node (ref "C19") (pin "1") (pinfunction "1_1") (pintype "passive"))
      (node (ref "C2") (pin "-") (pinfunction "-_-") (pintype "passive"))
      (node (ref "C3") (pin "2") (pinfunction "2_2") (pintype "passive"))
      (node (ref "C4") (pin "2") (pinfunction "2_2") (pintype "passive"))
      (node (ref "C5") (pin "2") (pinfunction "2_2") (pintype "passive"))
      (node (ref "LM1") (pin "1") (pinfunction "ADJ_1") (pintype "input"))
      (node (ref "R3") (pin "1") (pinfunction "1_1") (pintype "passive"))
      (node (ref "U$1") (pin "-VOUT") (pinfunction "-OUT_-VOUT") (pintype "bidirectional"))
      (node (ref "U$2") (pin "2") (pinfunction "2_2") (pintype "passive"))
      (node (ref "U$20") (pin "P$1") (pinfunction "T_P$1") (pintype "bidirectional"))
      (node (ref "U$9") (pin "P$3") (pinfunction "SHDN_P$3") (pintype "bidirectional"))
      (node (ref "U$9") (pin "P$4") (pinfunction "GND1_P$4") (pintype "bidirectional"))
    )
    (net (code "48") (name "GND") (class "Default")
      (node (ref "C10") (pin "2") (pinfunction "2_2") (pintype "passive"))
      (node (ref "C21") (pin "1") (pinfunction "1_1") (pintype "passive"))
      (node (ref "C22") (pin "1") (pinfunction "1_1") (pintype "passive"))
      (node (ref "C37") (pin "-") (pinfunction "-_-") (pintype "passive"))
      (node (ref "C38") (pin "-") (pinfunction "-_-") (pintype "passive"))
      (node (ref "C39") (pin "-") (pinfunction "-_-") (pintype "passive"))
      (node (ref "C41") (pin "1") (pinfunction "1_1") (pintype "passive"))
      (node (ref "C43") (pin "1") (pinfunction "1_1") (pintype "passive"))
      (node (ref "C44") (pin "1") (pinfunction "1_1") (pintype "passive"))
      (node (ref "C46") (pin "1") (pinfunction "1_1") (pintype "passive"))
      (node (ref "C47") (pin "1") (pinfunction "1_1") (pintype "passive"))
      (node (ref "C48") (pin "1") (pinfunction "1_1") (pintype "passive"))
      (node (ref "C49") (pin "1") (pinfunction "1_1") (pintype "passive"))
      (node (ref "C50") (pin "1") (pinfunction "1_1") (pintype "passive"))
      (node (ref "C53") (pin "1") (pinfunction "1_1") (pintype "passive"))
      (node (ref "C55") (pin "1") (pinfunction "1_1") (pintype "passive"))
      (node (ref "C56") (pin "1") (pinfunction "1_1") (pintype "passive"))
      (node (ref "C57") (pin "1") (pinfunction "1_1") (pintype "passive"))
      (node (ref "C58") (pin "1") (pinfunction "1_1") (pintype "passive"))
      (node (ref "C59") (pin "1") (pinfunction "1_1") (pintype "passive"))
      (node (ref "C6") (pin "1") (pinfunction "1_1") (pintype "passive"))
      (node (ref "C67") (pin "1") (pinfunction "1_1") (pintype "passive"))
      (node (ref "C68") (pin "1") (pinfunction "1_1") (pintype "passive"))
      (node (ref "C7") (pin "1") (pinfunction "1_1") (pintype "passive"))
      (node (ref "C8") (pin "1") (pinfunction "1_1") (pintype "passive"))
      (node (ref "C82") (pin "2") (pinfunction "2_2") (pintype "passive"))
      (node (ref "C9") (pin "1") (pinfunction "1_1") (pintype "passive"))
      (node (ref "C_CAP1") (pin "2") (pinfunction "2_2") (pintype "passive"))
      (node (ref "C_CAP2") (pin "2") (pinfunction "2_2") (pintype "passive"))
      (node (ref "C_VDDA2") (pin "2") (pinfunction "2_2") (pintype "passive"))
      (node (ref "C_VDDA3") (pin "1") (pinfunction "1_1") (pintype "passive"))
      (node (ref "D1") (pin "A") (pinfunction "A_A") (pintype "passive"))
      (node (ref "D34") (pin "A") (pinfunction "A_A") (pintype "passive"))
      (node (ref "GREEN") (pin "K") (pinfunction "C_K") (pintype "passive"))
      (node (ref "JP2") (pin "1") (pinfunction "1_1") (pintype "passive"))
      (node (ref "JP4") (pin "1") (pinfunction "1_1") (pintype "passive"))
      (node (ref "JP5") (pin "3") (pinfunction "3_3") (pintype "passive"))
      (node (ref "LD1117-33C") (pin "1") (pinfunction "ADJ_1") (pintype "input"))
      (node (ref "OK1") (pin "2") (pinfunction "C_2") (pintype "passive"))
      (node (ref "OK2") (pin "2") (pinfunction "C_2") (pintype "passive"))
      (node (ref "OK3") (pin "2") (pinfunction "C_2") (pintype "passive"))
      (node (ref "Q1") (pin "2") (pinfunction "E_2") (pintype "passive"))
      (node (ref "Q2") (pin "1") (pinfunction "S_1") (pintype "passive"))
      (node (ref "Q9") (pin "1") (pinfunction "S_1") (pintype "passive"))
      (node (ref "R15") (pin "2") (pinfunction "2_2") (pintype "passive"))
      (node (ref "R175") (pin "1") (pinfunction "1_1") (pintype "passive"))
      (node (ref "R29") (pin "2") (pinfunction "2_2") (pintype "passive"))
      (node (ref "R4") (pin "2") (pinfunction "2_2") (pintype "passive"))
      (node (ref "R6") (pin "1") (pinfunction "1_1") (pintype "passive"))
      (node (ref "R74") (pin "1") (pinfunction "1_1") (pintype "passive"))
      (node (ref "R9") (pin "1") (pinfunction "1_1") (pintype "passive"))
      (node (ref "R_TPS_DOWN1") (pin "2") (pinfunction "2_2") (pintype "passive"))
      (node (ref "R_TPS_DOWN2") (pin "2") (pinfunction "2_2") (pintype "passive"))
      (node (ref "U$1") (pin "-IN") (pinfunction "-IN_-IN") (pintype "bidirectional"))
      (node (ref "U$29") (pin "2") (pinfunction "GND_2") (pintype "bidirectional"))
      (node (ref "U$3") (pin "1") (pinfunction "1_1") (pintype "passive"))
      (node (ref "U$3") (pin "11") (pinfunction "11_11") (pintype "passive"))
      (node (ref "U$3") (pin "13") (pinfunction "13_13") (pintype "passive"))
      (node (ref "U$3") (pin "15") (pinfunction "15_15") (pintype "passive"))
      (node (ref "U$3") (pin "17") (pinfunction "17_17") (pintype "passive"))
      (node (ref "U$3") (pin "2") (pinfunction "2_2") (pintype "passive"))
      (node (ref "U$3") (pin "21") (pinfunction "21_21") (pintype "passive"))
      (node (ref "U$31") (pin "12") (pinfunction "VSSA_12") (pintype "bidirectional"))
      (node (ref "U$31") (pin "18") (pinfunction "VSS1_18") (pintype "bidirectional"))
      (node (ref "U$31") (pin "60") (pinfunction "BOOT0_60") (pintype "bidirectional"))
      (node (ref "U$31") (pin "63") (pinfunction "VSS2_63") (pintype "bidirectional"))
      (node (ref "U$32") (pin "P$4") (pinfunction "VSS_P$4") (pintype "bidirectional"))
      (node (ref "U$32") (pin "P$9") (pinfunction "GND_P$9") (pintype "bidirectional"))
      (node (ref "U$4") (pin "P$1") (pinfunction "T_P$1") (pintype "bidirectional"))
      (node (ref "U$70") (pin "4") (pinfunction "V-_4") (pintype "bidirectional"))
      (node (ref "U$9") (pin "P$5") (pinfunction "GND2_P$5") (pintype "bidirectional"))
      (node (ref "U8") (pin "P$2") (pinfunction "GND_P$2") (pintype "bidirectional"))
    )
    (net (code "49") (name "Net-(JP4-Pad2)") (class "Default")
      (node (ref "JP4") (pin "2") (pinfunction "2_2") (pintype "passive"))
      (node (ref "R174") (pin "2") (pinfunction "2_2") (pintype "passive"))
      (node (ref "R_CLT_UP2") (pin "1") (pinfunction "1_1") (pintype "passive"))
    )
    (net (code "50") (name "Net-(K1A-2)") (class "Default")
      (node (ref "K1") (pin "12") (pinfunction "2_12") (pintype "passive"))
      (node (ref "Q1") (pin "3") (pinfunction "C_3") (pintype "passive"))
      (node (ref "U$16") (pin "P$1") (pinfunction "T_P$1") (pintype "bidirectional"))
    )
    (net (code "51") (name "Net-(K1B-O)") (class "Default")
      (node (ref "K1") (pin "10") (pinfunction "O_10") (pintype "passive"))
      (node (ref "K1") (pin "3") (pinfunction "O_3") (pintype "passive"))
    )
    (net (code "52") (name "Net-(OK1-A)") (class "Default")
      (node (ref "OK1") (pin "1") (pinfunction "A_1") (pintype "passive"))
      (node (ref "R178") (pin "1") (pinfunction "1_1") (pintype "passive"))
    )
    (net (code "53") (name "Net-(OK1-EMIT)") (class "Default")
      (node (ref "OK1") (pin "3") (pinfunction "EMIT_3") (pintype "passive"))
      (node (ref "R171") (pin "2") (pinfunction "2_2") (pintype "passive"))
    )
    (net (code "54") (name "Net-(OK2-A)") (class "Default")
      (node (ref "OK2") (pin "1") (pinfunction "A_1") (pintype "passive"))
      (node (ref "R7") (pin "1") (pinfunction "1_1") (pintype "passive"))
    )
    (net (code "55") (name "Net-(OK2-EMIT)") (class "Default")
      (node (ref "OK2") (pin "3") (pinfunction "EMIT_3") (pintype "passive"))
      (node (ref "R8") (pin "2") (pinfunction "2_2") (pintype "passive"))
    )
    (net (code "56") (name "Net-(OK3-A)") (class "Default")
      (node (ref "OK3") (pin "1") (pinfunction "A_1") (pintype "passive"))
      (node (ref "R10") (pin "1") (pinfunction "1_1") (pintype "passive"))
    )
    (net (code "57") (name "Net-(OK3-EMIT)") (class "Default")
      (node (ref "OK3") (pin "3") (pinfunction "EMIT_3") (pintype "passive"))
      (node (ref "R11") (pin "2") (pinfunction "2_2") (pintype "passive"))
      (node (ref "R9") (pin "2") (pinfunction "2_2") (pintype "passive"))
    )
    (net (code "58") (name "Net-(Q1-B)") (class "Default")
      (node (ref "Q1") (pin "1") (pinfunction "B_1") (pintype "passive"))
      (node (ref "R4") (pin "1") (pinfunction "1_1") (pintype "passive"))
      (node (ref "R5") (pin "2") (pinfunction "2_2") (pintype "passive"))
    )
    (net (code "59") (name "Net-(Q2-G)") (class "Default")
      (node (ref "Q2") (pin "3") (pinfunction "G_3") (pintype "passive"))
      (node (ref "R6") (pin "2") (pinfunction "2_2") (pintype "passive"))
      (node (ref "R8") (pin "1") (pinfunction "1_1") (pintype "passive"))
    )
    (net (code "60") (name "Net-(Q9-G)") (class "Default")
      (node (ref "Q9") (pin "3") (pinfunction "G_3") (pintype "passive"))
      (node (ref "R171") (pin "1") (pinfunction "1_1") (pintype "passive"))
      (node (ref "R175") (pin "2") (pinfunction "2_2") (pintype "passive"))
    )
    (net (code "61") (name "Net-(R1-Pad2)") (class "Default")
      (node (ref "R1") (pin "2") (pinfunction "2_2") (pintype "passive"))
      (node (ref "R19") (pin "2") (pinfunction "2_2") (pintype "passive"))
    )
    (net (code "62") (name "Net-(R121-Pad1)") (class "Default")
      (node (ref "R121") (pin "1") (pinfunction "1_1") (pintype "passive"))
      (node (ref "R19") (pin "1") (pinfunction "1_1") (pintype "passive"))
      (node (ref "R3") (pin "2") (pinfunction "2_2") (pintype "passive"))
    )
    (net (code "63") (name "Net-(R179-Pad1)") (class "Default")
      (node (ref "R179") (pin "1") (pinfunction "1_1") (pintype "passive"))
      (node (ref "R_TPS1") (pin "2") (pinfunction "2_2") (pintype "passive"))
      (node (ref "R_TPS_DOWN1") (pin "1") (pinfunction "1_1") (pintype "passive"))
    )
    (net (code "64") (name "Net-(R180-Pad1)") (class "Default")
      (node (ref "R180") (pin "1") (pinfunction "1_1") (pintype "passive"))
      (node (ref "R_TPS2") (pin "2") (pinfunction "2_2") (pintype "passive"))
      (node (ref "R_TPS_DOWN2") (pin "1") (pinfunction "1_1") (pintype "passive"))
    )
    (net (code "65") (name "Net-(U$7-T)") (class "Default")
      (node (ref "GREEN") (pin "A") (pinfunction "A_A") (pintype "passive"))
      (node (ref "R173") (pin "1") (pinfunction "1_1") (pintype "passive"))
      (node (ref "U$7") (pin "P$1") (pinfunction "T_P$1") (pintype "bidirectional"))
    )
    (net (code "66") (name "Net-(U$9-VIN)") (class "Default")
      (node (ref "C19") (pin "2") (pinfunction "2_2") (pintype "passive"))
      (node (ref "R121") (pin "2") (pinfunction "2_2") (pintype "passive"))
      (node (ref "U$9") (pin "P$2") (pinfunction "VIN_P$2") (pintype "bidirectional"))
    )
    (net (code "67") (name "Net-(U$9-VOUT+)") (class "Default")
      (node (ref "R21") (pin "2") (pinfunction "2_2") (pintype "passive"))
      (node (ref "U$9") (pin "P$7") (pinfunction "VOUT+_P$7") (pintype "bidirectional"))
    )
    (net (code "68") (name "Net-(U$9-VOUT-)") (class "Default")
      (node (ref "R41") (pin "2") (pinfunction "2_2") (pintype "passive"))
      (node (ref "U$9") (pin "P$6") (pinfunction "VOUT-_P$6") (pintype "bidirectional"))
    )
    (net (code "69") (name "Net-(U$31-PC4)") (class "Default")
      (node (ref "R173") (pin "2") (pinfunction "2_2") (pintype "passive"))
      (node (ref "U$31") (pin "24") (pinfunction "PC4_24") (pintype "bidirectional"))
    )
    (net (code "70") (name "Net-(U$31-VCAP1)") (class "Default")
      (node (ref "C_CAP2") (pin "1") (pinfunction "1_1") (pintype "passive"))
      (node (ref "U$31") (pin "31") (pinfunction "VCAP1_31") (pintype "bidirectional"))
    )
    (net (code "71") (name "Net-(U$31-VCAP2)") (class "Default")
      (node (ref "C_CAP1") (pin "1") (pinfunction "1_1") (pintype "passive"))
      (node (ref "U$31") (pin "47") (pinfunction "VCAP2_47") (pintype "bidirectional"))
    )
    (net (code "72") (name "Net-(U$31-VDDA)") (class "Default")
      (node (ref "C_VDDA2") (pin "1") (pinfunction "1_1") (pintype "passive"))
      (node (ref "INDUCTOR") (pin "2") (pinfunction "2_2") (pintype "passive"))
      (node (ref "U$31") (pin "13") (pinfunction "VDDA_13") (pintype "bidirectional"))
    )
    (net (code "73") (name "Net-(U$70-+IN)") (class "Default")
      (node (ref "C82") (pin "1") (pinfunction "1_1") (pintype "passive"))
      (node (ref "R21") (pin "1") (pinfunction "1_1") (pintype "passive"))
      (node (ref "R29") (pin "1") (pinfunction "1_1") (pintype "passive"))
      (node (ref "U$70") (pin "3") (pinfunction "+IN_3") (pintype "bidirectional"))
    )
    (net (code "74") (name "Net-(U$70--IN)") (class "Default")
      (node (ref "C81") (pin "2") (pinfunction "2_2") (pintype "passive"))
      (node (ref "R41") (pin "1") (pinfunction "1_1") (pintype "passive"))
      (node (ref "R60") (pin "2") (pinfunction "2_2") (pintype "passive"))
      (node (ref "U$70") (pin "2") (pinfunction "-IN_2") (pintype "bidirectional"))
    )
    (net (code "75") (name "Net-(U$70-OUT)") (class "Default")
      (node (ref "C81") (pin "1") (pinfunction "1_1") (pintype "passive"))
      (node (ref "R20") (pin "2") (pinfunction "2_2") (pintype "passive"))
      (node (ref "R60") (pin "1") (pinfunction "1_1") (pintype "passive"))
      (node (ref "U$70") (pin "6") (pinfunction "OUT_6") (pintype "bidirectional"))
    )
    (net (code "76") (name "Net-(U8-RS)") (class "Default")
      (node (ref "R74") (pin "2") (pinfunction "2_2") (pintype "passive"))
      (node (ref "U8") (pin "P$8") (pinfunction "RS_P$8") (pintype "bidirectional"))
    )
    (net (code "77") (name "VCC") (class "Default")
      (node (ref "C10") (pin "1") (pinfunction "1_1") (pintype "passive"))
      (node (ref "C21") (pin "2") (pinfunction "2_2") (pintype "passive"))
      (node (ref "C39") (pin "+") (pinfunction "+_+") (pintype "passive"))
      (node (ref "C57") (pin "2") (pinfunction "2_2") (pintype "passive"))
      (node (ref "C6") (pin "2") (pinfunction "2_2") (pintype "passive"))
      (node (ref "C68") (pin "2") (pinfunction "2_2") (pintype "passive"))
      (node (ref "LD1117-33C") (pin "3") (pinfunction "IN_3") (pintype "input"))
      (node (ref "U$29") (pin "3") (pinfunction "OUT_3") (pintype "bidirectional"))
      (node (ref "U$3") (pin "22") (pinfunction "22_22") (pintype "passive"))
      (node (ref "U$35") (pin "P$1") (pinfunction "T_P$1") (pintype "bidirectional"))
      (node (ref "U$70") (pin "7") (pinfunction "V+_7") (pintype "bidirectional"))
      (node (ref "U$9") (pin "P$8") (pinfunction "VDD2_P$8") (pintype "bidirectional"))
      (node (ref "U8") (pin "P$3") (pinfunction "VCC_P$3") (pintype "bidirectional"))
    )
    (net (code "78") (name "VCCIO") (class "Default")
      (node (ref "C1") (pin "+") (pinfunction "+_+") (pintype "passive"))
      (node (ref "C4") (pin "1") (pinfunction "1_1") (pintype "passive"))
      (node (ref "C5") (pin "1") (pinfunction "1_1") (pintype "passive"))
      (node (ref "LM1") (pin "4") (pinfunction "OUT_4") (pintype "passive"))
      (node (ref "U$19") (pin "P$1") (pinfunction "T_P$1") (pintype "bidirectional"))
      (node (ref "U$9") (pin "P$1") (pinfunction "VDD1_P$1") (pintype "bidirectional"))
    )
    (net (code "79") (name "VDD") (class "Default")
      (node (ref "C37") (pin "+") (pinfunction "+_+") (pintype "passive"))
      (node (ref "C41") (pin "2") (pinfunction "2_2") (pintype "passive"))
      (node (ref "C46") (pin "2") (pinfunction "2_2") (pintype "passive"))
      (node (ref "C47") (pin "2") (pinfunction "2_2") (pintype "passive"))
      (node (ref "C48") (pin "2") (pinfunction "2_2") (pintype "passive"))
      (node (ref "C49") (pin "2") (pinfunction "2_2") (pintype "passive"))
      (node (ref "C53") (pin "2") (pinfunction "2_2") (pintype "passive"))
      (node (ref "C_VDDA3") (pin "2") (pinfunction "2_2") (pintype "passive"))
      (node (ref "INDUCTOR") (pin "1") (pinfunction "1_1") (pintype "passive"))
      (node (ref "JP2") (pin "6") (pinfunction "6_6") (pintype "passive"))
      (node (ref "JP5") (pin "1") (pinfunction "1_1") (pintype "passive"))
      (node (ref "LD1117-33C") (pin "4") (pinfunction "OUT_4") (pintype "passive"))
      (node (ref "OK3") (pin "4") (pinfunction "COL_4") (pintype "passive"))
      (node (ref "R182") (pin "2") (pinfunction "2_2") (pintype "passive"))
      (node (ref "R_CLT_UP1") (pin "2") (pinfunction "2_2") (pintype "passive"))
      (node (ref "R_CLT_UP2") (pin "2") (pinfunction "2_2") (pintype "passive"))
      (node (ref "R_CLT_UP3") (pin "2") (pinfunction "2_2") (pintype "passive"))
      (node (ref "R_CLT_UP4") (pin "2") (pinfunction "2_2") (pintype "passive"))
      (node (ref "R_CLT_UP5") (pin "2") (pinfunction "2_2") (pintype "passive"))
      (node (ref "U$31") (pin "1") (pinfunction "VBATT_1") (pintype "bidirectional"))
      (node (ref "U$31") (pin "19") (pinfunction "VDD1_19") (pintype "bidirectional"))
      (node (ref "U$31") (pin "32") (pinfunction "VDD2_32") (pintype "bidirectional"))
      (node (ref "U$31") (pin "48") (pinfunction "VDD3_48") (pintype "bidirectional"))
      (node (ref "U$31") (pin "64") (pinfunction "VDD4_64") (pintype "bidirectional"))
      (node (ref "U$32") (pin "P$8") (pinfunction "VDD_P$8") (pintype "bidirectional"))
      (node (ref "U$6") (pin "P$1") (pinfunction "T_P$1") (pintype "bidirectional"))
    )
    (net (code "80") (name "VPP") (class "Default")
      (node (ref "C2") (pin "+") (pinfunction "+_+") (pintype "passive"))
      (node (ref "C3") (pin "1") (pinfunction "1_1") (pintype "passive"))
      (node (ref "LM1") (pin "3") (pinfunction "IN_3") (pintype "input"))
      (node (ref "U$1") (pin "+VOUT") (pinfunction "+OUT_+VOUT") (pintype "bidirectional"))
      (node (ref "U$21") (pin "P$1") (pinfunction "T_P$1") (pintype "bidirectional"))
    )
    (net (code "81") (name "unconnected-(U$2-Pad1)") (class "Default")
      (node (ref "U$2") (pin "1") (pinfunction "1_1") (pintype "passive"))
    )
    (net (code "82") (name "unconnected-(U$2-Pad3)") (class "Default")
      (node (ref "U$2") (pin "3") (pinfunction "3_3") (pintype "passive"))
    )
    (net (code "83") (name "unconnected-(U$2-Pad4)") (class "Default")
      (node (ref "U$2") (pin "4") (pinfunction "4_4") (pintype "passive"))
    )
    (net (code "84") (name "unconnected-(U$2-Pad5)") (class "Default")
      (node (ref "U$2") (pin "5") (pinfunction "5_5") (pintype "passive"))
    )
    (net (code "85") (name "unconnected-(U$2-Pad6)") (class "Default")
      (node (ref "U$2") (pin "6") (pinfunction "6_6") (pintype "passive"))
    )
    (net (code "86") (name "unconnected-(U$2-Pad7)") (class "Default")
      (node (ref "U$2") (pin "7") (pinfunction "7_7") (pintype "passive"))
    )
    (net (code "87") (name "unconnected-(U$31-PA8-Pad41)") (class "Default")
      (node (ref "U$31") (pin "41") (pinfunction "PA8_41") (pintype "bidirectional"))
    )
    (net (code "88") (name "unconnected-(U$31-PA11-Pad44)") (class "Default")
      (node (ref "U$31") (pin "44") (pinfunction "PA11_44") (pintype "bidirectional"))
    )
    (net (code "89") (name "unconnected-(U$31-PA15-Pad50)") (class "Default")
      (node (ref "U$31") (pin "50") (pinfunction "PA15_50") (pintype "bidirectional"))
    )
    (net (code "90") (name "unconnected-(U$31-PB0-Pad26)") (class "Default")
      (node (ref "U$31") (pin "26") (pinfunction "PB0_26") (pintype "bidirectional"))
    )
    (net (code "91") (name "unconnected-(U$31-PB2-Pad28)") (class "Default")
      (node (ref "U$31") (pin "28") (pinfunction "PB2_28") (pintype "bidirectional"))
    )
    (net (code "92") (name "unconnected-(U$31-PB6-Pad58)") (class "Default")
      (node (ref "U$31") (pin "58") (pinfunction "PB6_58") (pintype "bidirectional"))
    )
    (net (code "93") (name "unconnected-(U$31-PB11-Pad30)") (class "Default")
      (node (ref "U$31") (pin "30") (pinfunction "PB11_30") (pintype "bidirectional"))
    )
    (net (code "94") (name "unconnected-(U$31-PB15-Pad36)") (class "Default")
      (node (ref "U$31") (pin "36") (pinfunction "PB15_36") (pintype "bidirectional"))
    )
    (net (code "95") (name "unconnected-(U$31-PC0-Pad8)") (class "Default")
      (node (ref "U$31") (pin "8") (pinfunction "PC0_8") (pintype "bidirectional"))
    )
    (net (code "96") (name "unconnected-(U$31-PC1-Pad9)") (class "Default")
      (node (ref "U$31") (pin "9") (pinfunction "PC1_9") (pintype "bidirectional"))
    )
    (net (code "97") (name "unconnected-(U$31-PC8-Pad39)") (class "Default")
      (node (ref "U$31") (pin "39") (pinfunction "PC8_39") (pintype "bidirectional"))
    )
    (net (code "98") (name "unconnected-(U$31-PC9-Pad40)") (class "Default")
      (node (ref "U$31") (pin "40") (pinfunction "PC9_40") (pintype "bidirectional"))
    )
    (net (code "99") (name "unconnected-(U$31-PC10-Pad51)") (class "Default")
      (node (ref "U$31") (pin "51") (pinfunction "PC10_51") (pintype "bidirectional"))
    )
    (net (code "100") (name "unconnected-(U$31-PC11-Pad52)") (class "Default")
      (node (ref "U$31") (pin "52") (pinfunction "PC11_52") (pintype "bidirectional"))
    )
    (net (code "101") (name "unconnected-(U$31-PC13-Pad2)") (class "Default")
      (node (ref "U$31") (pin "2") (pinfunction "PC13_2") (pintype "bidirectional"))
    )
    (net (code "102") (name "unconnected-(U$31-PC14-Pad3)") (class "Default")
      (node (ref "U$31") (pin "3") (pinfunction "PC14_3") (pintype "bidirectional"))
    )
    (net (code "103") (name "unconnected-(U$31-PC15-Pad4)") (class "Default")
      (node (ref "U$31") (pin "4") (pinfunction "PC15_4") (pintype "bidirectional"))
    )
    (net (code "104") (name "unconnected-(U$31-PD2-Pad54)") (class "Default")
      (node (ref "U$31") (pin "54") (pinfunction "PD2_54") (pintype "bidirectional"))
    )
    (net (code "105") (name "unconnected-(U$31-PH0_OSC_IN-Pad5)") (class "Default")
      (node (ref "U$31") (pin "5") (pinfunction "PH0_OSC_IN_5") (pintype "bidirectional"))
    )
    (net (code "106") (name "unconnected-(U$31-PH1_OSC_OUT-Pad6)") (class "Default")
      (node (ref "U$31") (pin "6") (pinfunction "PH1_OSC_OUT_6") (pintype "bidirectional"))
    )
    (net (code "107") (name "unconnected-(U$70-NC-Pad1)") (class "Default")
      (node (ref "U$70") (pin "1") (pinfunction "NC_1") (pintype "bidirectional"))
    )
    (net (code "108") (name "unconnected-(U$70-NC2-Pad5)") (class "Default")
      (node (ref "U$70") (pin "5") (pinfunction "NC2_5") (pintype "bidirectional"))
    )
    (net (code "109") (name "unconnected-(U$70-NC3-Pad8)") (class "Default")
      (node (ref "U$70") (pin "8") (pinfunction "NC3_8") (pintype "bidirectional"))
    )
    (net (code "110") (name "unconnected-(U8-VREF-PadP$5)") (class "Default")
      (node (ref "U8") (pin "P$5") (pinfunction "VREF_P$5") (pintype "bidirectional"))
    )
  )
)
